# Sheet1.net
KiCad netlist of a schematic drawn in Altium Designer
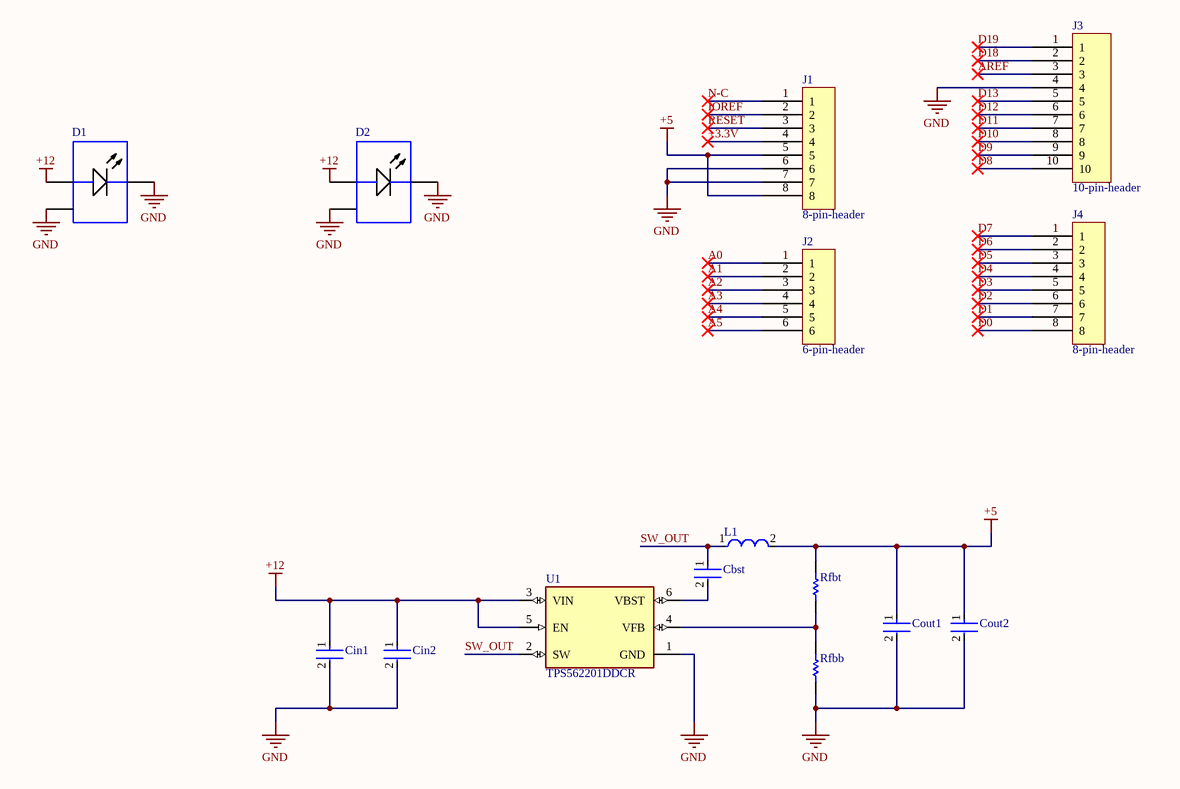
[diagram p0: Sheet1.SchDoc]

(export (version "E")
  (design (tool "Eeschema 10.0.6"))
  (components
    (comp (ref "Cbst")
      (value "CL10B104KA8NFNC")
      (footprint "FP-CL10-IPC_C")
      (description "Cap Ceramic 100nF 25V X7R ±10% Pad SMD 0603 +125°C T/R")
      (fields (field (name "TOLERANCE") "10%"))
      (libsource (lib "Altium Content Vault") (part "b4654b650e69147ec39a6b967a45e02"))
    )
    (comp (ref "Cin1")
      (value "CL21A106MPFNNNF")
      (footprint "FP-CL21-IPC_C")
      (description "CL21 Series 0805 10uF 10V ±20% Tolerance X5R Multilayer Ceramic Chip Capacitor")
      (fields (field (name "TOLERANCE") "20%"))
      (libsource (lib "Altium Content Vault") (part "b4654b650e69147ec39a6b967a45e02"))
    )
    (comp (ref "Cin2")
      (value "CL21A106MPFNNNF")
      (footprint "FP-CL21-IPC_C")
      (description "CL21 Series 0805 10uF 10V ±20% Tolerance X5R Multilayer Ceramic Chip Capacitor")
      (fields (field (name "TOLERANCE") "20%"))
      (libsource (lib "Altium Content Vault") (part "b4654b650e69147ec39a6b967a45e02"))
    )
    (comp (ref "Cout1")
      (value "12066D226MAT2A")
      (footprint "FP-1206-L_3_2_0_2-W_1_6_0-IPC_C")
      (description "General Purpose Ceramic Capacitor, 1206, 22uF, 20%, X5R, 15%, 6.3V")
      (fields (field (name "TOLERANCE") "20%") (field (name "VOLTAGE") "6.3V"))
      (libsource (lib "Altium Content Vault") (part "02cd4be3c70576c341d710602a673aa"))
    )
    (comp (ref "Cout2")
      (value "12066D226MAT2A")
      (footprint "FP-1206-L_3_2_0_2-W_1_6_0-IPC_C")
      (description "General Purpose Ceramic Capacitor, 1206, 22uF, 20%, X5R, 15%, 6.3V")
      (fields (field (name "TOLERANCE") "20%") (field (name "VOLTAGE") "6.3V"))
      (libsource (lib "Altium Content Vault") (part "02cd4be3c70576c341d710602a673aa"))
    )
    (comp (ref "D1")
      (value "MKRAWT-00-0000-0D0BJ20E5")
      (footprint "CREE-MK-R-2_V")
      (description "LED, White, 12 V, 2-Pin SMD, RoHS, Tape and Reel")
      (libsource (lib "Altium Content Vault") (part "LED_WHITE-3"))
    )
    (comp (ref "D2")
      (value "MKRAWT-00-0000-0D0BJ20E5")
      (footprint "CREE-MK-R-2_V")
      (description "LED, White, 12 V, 2-Pin SMD, RoHS, Tape and Reel")
      (fields
        (field (name "MANUFACTURER") "Texas Instruments")
        (field (name "MANUFACTURER PART NUMBER") "TPS562200DDCR")
      )
      (libsource (lib "Altium Content Vault") (part "LED_WHITE-3"))
    )
    (comp (ref "J1")
      (value "8-pin-header")
      (footprint "8-pin-header-Footprint-1")
      (description "8 pin header for arduino")
      (libsource (lib "Hash's workspace") (part "8-pin-header-Symbol-1"))
    )
    (comp (ref "J2")
      (value "6-pin-header")
      (footprint "6-pin-header-Footprint-1")
      (description "1x6 pin header for arduino")
      (libsource (lib "Hash's workspace") (part "6-pin-header-Symbol-1"))
    )
    (comp (ref "J3")
      (value "10-pin-header")
      (footprint "10-pin-header-Footprint-1")
      (description "10 pin header for arduino")
      (libsource (lib "Hash's workspace") (part "10-pin-header-Symbol-1"))
    )
    (comp (ref "J4")
      (value "8-pin-header")
      (footprint "8-pin-header-Footprint-1")
      (description "8 pin header for arduino")
      (libsource (lib "Hash's workspace") (part "8-pin-header-Symbol-1"))
    )
    (comp (ref "L1")
      (value "NRS8030T3R3MJGJ")
      (footprint "FP-NRS8030-MFG")
      (description "Inductor Power Shielded Wirewound 3.3uH 20% 100KHz Ferrite 4.2A 24.7mΩ DCR T/R")
      (fields (field (name "TOLERANCE") "20%"))
      (libsource (lib "Altium Content Vault") (part "725321dda6339637d4d059423bc1c3c"))
    )
    (comp (ref "Rfbb")
      (value "ERJ2RKF1002X")
      (footprint "RESC1005X40X25LL05T05")
      (description "Chip Resistor, 10 KOhm, +/- 1%, 0.1 W, -55 to 155 degC, 0402 (1005 Metric), RoHS, Tape and Reel")
      (fields (field (name "TOLERANCE") "1%") (field (name "MANUFACTURER") "Panasonic"))
      (libsource (lib "Altium Content Vault") (part "RES-2"))
    )
    (comp (ref "Rfbt")
      (value "ERJ-2RKF5622X")
      (footprint "RESC1005X40X25LL05T05")
      (fields (field (name "MANUFACTURER") "Panasonic"))
      (libsource (lib "Altium Content Vault") (part "RES"))
    )
    (comp (ref "U1")
      (value "TPS562201DDCR")
      (footprint "FP-DDC0006A-IPC_C")
      (description "IC REG BUCK ADJ 2A TSOT23-6")
      (libsource (lib "Altium Content Vault") (part "957e164956730ea4bf6293280af19fc"))
    )
  )
  (nets
    (net (code "1") (name "+5") (class "Default")
      (node (ref "Cout1") (pin "1") (pinfunction "1_1") (pintype "passive"))
      (node (ref "Cout2") (pin "1") (pinfunction "1_1") (pintype "passive"))
      (node (ref "J1") (pin "5") (pinfunction "5_5") (pintype "passive"))
      (node (ref "J1") (pin "8") (pinfunction "8_8") (pintype "passive"))
      (node (ref "L1") (pin "2") (pinfunction "2_2") (pintype "passive"))
      (node (ref "Rfbt") (pin "2") (pinfunction "2_2") (pintype "passive"))
    )
    (net (code "2") (name "+12") (class "Default")
      (node (ref "Cin1") (pin "1") (pinfunction "1_1") (pintype "passive"))
      (node (ref "Cin2") (pin "1") (pinfunction "1_1") (pintype "passive"))
      (node (ref "D1") (pin "1") (pinfunction "A_1") (pintype "passive"))
      (node (ref "D2") (pin "1") (pinfunction "A_1") (pintype "passive"))
      (node (ref "U1") (pin "3") (pinfunction "VIN_3") (pintype "bidirectional"))
      (node (ref "U1") (pin "5") (pinfunction "EN_5") (pintype "input"))
    )
    (net (code "3") (name "/+3.3V") (class "Default")
      (node (ref "J1") (pin "4") (pinfunction "4_4") (pintype "passive+no_connect"))
    )
    (net (code "4") (name "/A0") (class "Default")
      (node (ref "J2") (pin "1") (pinfunction "1_1") (pintype "passive+no_connect"))
    )
    (net (code "5") (name "/A1") (class "Default")
      (node (ref "J2") (pin "2") (pinfunction "2_2") (pintype "passive+no_connect"))
    )
    (net (code "6") (name "/A2") (class "Default")
      (node (ref "J2") (pin "3") (pinfunction "3_3") (pintype "passive+no_connect"))
    )
    (net (code "7") (name "/A3") (class "Default")
      (node (ref "J2") (pin "4") (pinfunction "4_4") (pintype "passive+no_connect"))
    )
    (net (code "8") (name "/A4") (class "Default")
      (node (ref "J2") (pin "5") (pinfunction "5_5") (pintype "passive+no_connect"))
    )
    (net (code "9") (name "/A5") (class "Default")
      (node (ref "J2") (pin "6") (pinfunction "6_6") (pintype "passive+no_connect"))
    )
    (net (code "10") (name "/AREF") (class "Default")
      (node (ref "J3") (pin "3") (pinfunction "3_3") (pintype "passive+no_connect"))
    )
    (net (code "11") (name "/D0") (class "Default")
      (node (ref "J4") (pin "8") (pinfunction "8_8") (pintype "passive+no_connect"))
    )
    (net (code "12") (name "/D1") (class "Default")
      (node (ref "J4") (pin "7") (pinfunction "7_7") (pintype "passive+no_connect"))
    )
    (net (code "13") (name "/D2") (class "Default")
      (node (ref "J4") (pin "6") (pinfunction "6_6") (pintype "passive+no_connect"))
    )
    (net (code "14") (name "/D3") (class "Default")
      (node (ref "J4") (pin "5") (pinfunction "5_5") (pintype "passive+no_connect"))
    )
    (net (code "15") (name "/D4") (class "Default")
      (node (ref "J4") (pin "4") (pinfunction "4_4") (pintype "passive+no_connect"))
    )
    (net (code "16") (name "/D5") (class "Default")
      (node (ref "J4") (pin "3") (pinfunction "3_3") (pintype "passive+no_connect"))
    )
    (net (code "17") (name "/D6") (class "Default")
      (node (ref "J4") (pin "2") (pinfunction "2_2") (pintype "passive+no_connect"))
    )
    (net (code "18") (name "/D7") (class "Default")
      (node (ref "J4") (pin "1") (pinfunction "1_1") (pintype "passive+no_connect"))
    )
    (net (code "19") (name "/D8") (class "Default")
      (node (ref "J3") (pin "10") (pinfunction "10_10") (pintype "passive+no_connect"))
    )
    (net (code "20") (name "/D9") (class "Default")
      (node (ref "J3") (pin "9") (pinfunction "9_9") (pintype "passive+no_connect"))
    )
    (net (code "21") (name "/D10") (class "Default")
      (node (ref "J3") (pin "8") (pinfunction "8_8") (pintype "passive+no_connect"))
    )
    (net (code "22") (name "/D11") (class "Default")
      (node (ref "J3") (pin "7") (pinfunction "7_7") (pintype "passive+no_connect"))
    )
    (net (code "23") (name "/D12") (class "Default")
      (node (ref "J3") (pin "6") (pinfunction "6_6") (pintype "passive+no_connect"))
    )
    (net (code "24") (name "/D13") (class "Default")
      (node (ref "J3") (pin "5") (pinfunction "5_5") (pintype "passive+no_connect"))
    )
    (net (code "25") (name "/D18") (class "Default")
      (node (ref "J3") (pin "2") (pinfunction "2_2") (pintype "passive+no_connect"))
    )
    (net (code "26") (name "/D19") (class "Default")
      (node (ref "J3") (pin "1") (pinfunction "1_1") (pintype "passive+no_connect"))
    )
    (net (code "27") (name "/IOREF") (class "Default")
      (node (ref "J1") (pin "2") (pinfunction "2_2") (pintype "passive+no_connect"))
    )
    (net (code "28") (name "/N-C") (class "Default")
      (node (ref "J1") (pin "1") (pinfunction "1_1") (pintype "passive+no_connect"))
    )
    (net (code "29") (name "/RESET") (class "Default")
      (node (ref "J1") (pin "3") (pinfunction "3_3") (pintype "passive+no_connect"))
    )
    (net (code "30") (name "/SW_OUT") (class "Default")
      (node (ref "Cbst") (pin "1") (pinfunction "1_1") (pintype "passive"))
      (node (ref "L1") (pin "1") (pinfunction "1_1") (pintype "passive"))
      (node (ref "U1") (pin "2") (pinfunction "SW_2") (pintype "bidirectional"))
    )
    (net (code "31") (name "GND") (class "Default")
      (node (ref "Cin1") (pin "2") (pinfunction "2_2") (pintype "passive"))
      (node (ref "Cin2") (pin "2") (pinfunction "2_2") (pintype "passive"))
      (node (ref "Cout1") (pin "2") (pinfunction "2_2") (pintype "passive"))
      (node (ref "Cout2") (pin "2") (pinfunction "2_2") (pintype "passive"))
      (node (ref "D1") (pin "2") (pinfunction "K_2") (pintype "passive"))
      (node (ref "D1") (pin "3") (pinfunction "EP_3") (pintype "passive"))
      (node (ref "D2") (pin "2") (pinfunction "K_2") (pintype "passive"))
      (node (ref "D2") (pin "3") (pinfunction "EP_3") (pintype "passive"))
      (node (ref "J1") (pin "6") (pinfunction "6_6") (pintype "passive"))
      (node (ref "J1") (pin "7") (pinfunction "7_7") (pintype "passive"))
      (node (ref "J3") (pin "4") (pinfunction "4_4") (pintype "passive"))
      (node (ref "Rfbb") (pin "1") (pinfunction "1_1") (pintype "passive"))
      (node (ref "U1") (pin "1") (pinfunction "GND_1") (pintype "power_in"))
    )
    (net (code "32") (name "Net-(U1-VBST)") (class "Default")
      (node (ref "Cbst") (pin "2") (pinfunction "2_2") (pintype "passive"))
      (node (ref "U1") (pin "6") (pinfunction "VBST_6") (pintype "bidirectional"))
    )
    (net (code "33") (name "Net-(U1-VFB)") (class "Default")
      (node (ref "Rfbb") (pin "2") (pinfunction "2_2") (pintype "passive"))
      (node (ref "Rfbt") (pin "1") (pinfunction "1_1") (pintype "passive"))
      (node (ref "U1") (pin "4") (pinfunction "VFB_4") (pintype "bidirectional"))
    )
  )
)
